# utilidong-lipo-charger-mk-2_1.net
KiCad netlist of a schematic drawn in EAGLE
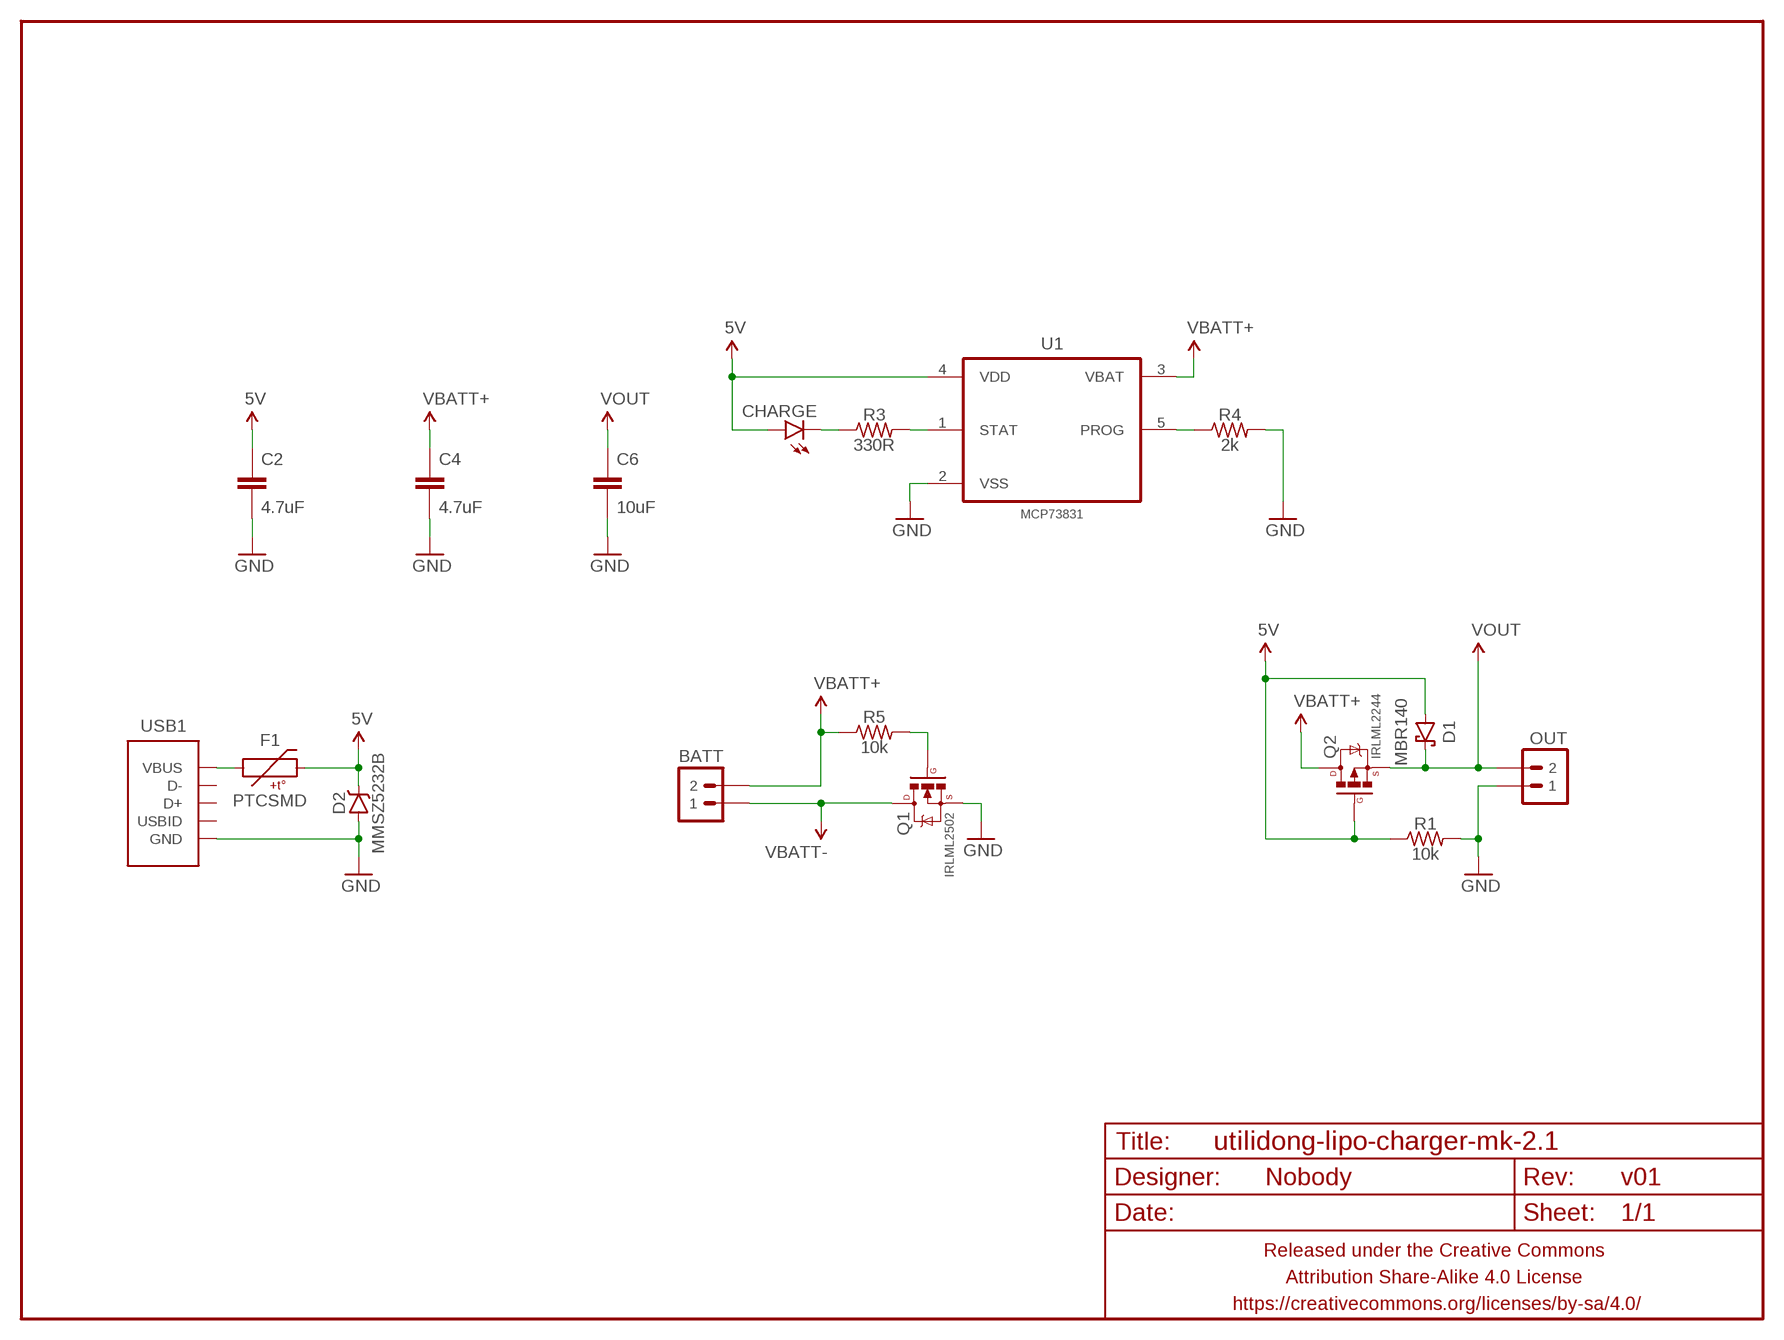
[diagram p0: schematic, sheet 1]

(export (version "E")
  (design (tool "Eeschema 10.0.6"))
  (components
    (comp (ref "BATT")
      (value "M02PTH-CENTERED-R+")
      (footprint "eagle-import:1X02-CENTER-R+")
      (libsource (lib "eagle-import") (part "M02PTH-CENTERED-R+"))
    )
    (comp (ref "C2")
      (value "4.7uF")
      (footprint "eagle-import:C0805")
      (libsource (lib "eagle-import") (part "CAPACITOR-CERAMICC0805"))
    )
    (comp (ref "C4")
      (value "4.7uF")
      (footprint "eagle-import:C0805")
      (libsource (lib "eagle-import") (part "CAPACITOR-CERAMICC0805"))
    )
    (comp (ref "C6")
      (value "10uF")
      (footprint "eagle-import:C0805")
      (libsource (lib "eagle-import") (part "CAPACITOR-CERAMICC0805"))
    )
    (comp (ref "CHARGE")
      (value "LED1206")
      (footprint "eagle-import:LED-1206")
      (libsource (lib "eagle-import") (part "LED1206"))
    )
    (comp (ref "D1")
      (value "MBR140")
      (footprint "eagle-import:SMA-DIODE-SCHOTTKY")
      (libsource (lib "eagle-import") (part "DIODE-SCHOTTKYSMA"))
    )
    (comp (ref "D2")
      (value "MMSZ5232B")
      (footprint "eagle-import:SOD123-ZENER")
      (libsource (lib "eagle-import") (part "DIODE-ZENERSOD123"))
    )
    (comp (ref "F1")
      (value "PTCSMD")
      (footprint "eagle-import:PTC-1206")
      (libsource (lib "eagle-import") (part "PTCSMD"))
    )
    (comp (ref "FRAME1")
      (value "FRAME-LETTERNO_PACKAGE")
      (footprint "eagle-import:DUMMY")
      (fields (field (name "DESIGNER") "Nobody"))
      (libsource (lib "eagle-import") (part "FRAME-LETTERNO_PACKAGE"))
    )
    (comp (ref "OUT")
      (value "M02PTH-CENTERED-R+")
      (footprint "eagle-import:1X02-CENTER-R+")
      (libsource (lib "eagle-import") (part "M02PTH-CENTERED-R+"))
    )
    (comp (ref "Q1")
      (value "IRLML2502")
      (footprint "eagle-import:SOT23")
      (libsource (lib "eagle-import") (part "MOSFET-NCHANNELBSS138"))
    )
    (comp (ref "Q2")
      (value "IRLML2244")
      (footprint "eagle-import:SOT23-3")
      (libsource (lib "eagle-import") (part "MOSFET-PCHANNELIRLML2244"))
    )
    (comp (ref "R1")
      (value "10k")
      (footprint "eagle-import:R0805")
      (libsource (lib "eagle-import") (part "RESISTORR0805"))
    )
    (comp (ref "R3")
      (value "330R")
      (footprint "eagle-import:R0805")
      (libsource (lib "eagle-import") (part "RESISTORR0805"))
    )
    (comp (ref "R4")
      (value "2k")
      (footprint "eagle-import:R0805")
      (libsource (lib "eagle-import") (part "RESISTORR0805"))
    )
    (comp (ref "R5")
      (value "10k")
      (footprint "eagle-import:R0805")
      (libsource (lib "eagle-import") (part "RESISTORR0805"))
    )
    (comp (ref "U1")
      (value "MCP73831")
      (footprint "eagle-import:SOT95P280X145-5N")
      (fields (field (name "MPN") "MCP73831T-2ACI/OT"))
      (libsource (lib "eagle-import") (part "MCP73831T-2ACI/OT"))
    )
    (comp (ref "USB1")
      (value "USB-ABCOMBO")
      (footprint "eagle-import:USB-MICRO-B-FCI-CUTOUT")
      (libsource (lib "eagle-import") (part "USB-ABCOMBO"))
    )
  )
  (nets
    (net (code "1") (name "5V") (class "Default")
      (node (ref "C2") (pin "1") (pinfunction "1_1") (pintype "passive"))
      (node (ref "CHARGE") (pin "A") (pinfunction "A_A") (pintype "passive"))
      (node (ref "D1") (pin "A") (pinfunction "A_A") (pintype "passive"))
      (node (ref "D2") (pin "C") (pinfunction "C_C") (pintype "passive"))
      (node (ref "F1") (pin "2") (pinfunction "2_2") (pintype "passive"))
      (node (ref "Q2") (pin "1") (pinfunction "G_1") (pintype "passive"))
      (node (ref "R1") (pin "1") (pinfunction "1_1") (pintype "passive"))
      (node (ref "U1") (pin "4") (pinfunction "VDD_4") (pintype "power_in"))
    )
    (net (code "2") (name "GND") (class "Default")
      (node (ref "C2") (pin "2") (pinfunction "2_2") (pintype "passive"))
      (node (ref "C4") (pin "2") (pinfunction "2_2") (pintype "passive"))
      (node (ref "C6") (pin "2") (pinfunction "2_2") (pintype "passive"))
      (node (ref "D2") (pin "A") (pinfunction "A_A") (pintype "passive"))
      (node (ref "OUT") (pin "1") (pinfunction "1_1") (pintype "passive"))
      (node (ref "Q1") (pin "2") (pinfunction "S_2") (pintype "passive"))
      (node (ref "R1") (pin "2") (pinfunction "2_2") (pintype "passive"))
      (node (ref "R4") (pin "2") (pinfunction "2_2") (pintype "passive"))
      (node (ref "U1") (pin "2") (pinfunction "VSS_2") (pintype "power_in"))
      (node (ref "USB1") (pin "5") (pinfunction "GND_5") (pintype "bidirectional"))
      (node (ref "USB1") (pin "P$1") (pinfunction "GND_P$1") (pintype "bidirectional"))
      (node (ref "USB1") (pin "P$2") (pinfunction "GND_P$2") (pintype "bidirectional"))
    )
    (net (code "3") (name "Net-(CHARGE-PadC)") (class "Default")
      (node (ref "CHARGE") (pin "C") (pinfunction "C_C") (pintype "passive"))
      (node (ref "R3") (pin "1") (pinfunction "1_1") (pintype "passive"))
    )
    (net (code "4") (name "Net-(Q1-G)") (class "Default")
      (node (ref "Q1") (pin "1") (pinfunction "G_1") (pintype "passive"))
      (node (ref "R5") (pin "2") (pinfunction "2_2") (pintype "passive"))
    )
    (net (code "5") (name "Net-(U1-PROG)") (class "Default")
      (node (ref "R4") (pin "1") (pinfunction "1_1") (pintype "passive"))
      (node (ref "U1") (pin "5") (pinfunction "PROG_5") (pintype "input"))
    )
    (net (code "6") (name "Net-(U1-STAT)") (class "Default")
      (node (ref "R3") (pin "2") (pinfunction "2_2") (pintype "passive"))
      (node (ref "U1") (pin "1") (pinfunction "STAT_1") (pintype "output"))
    )
    (net (code "7") (name "Net-(USB1-VBUS)") (class "Default")
      (node (ref "F1") (pin "1") (pinfunction "1_1") (pintype "passive"))
      (node (ref "USB1") (pin "1") (pinfunction "VBUS_1") (pintype "bidirectional"))
    )
    (net (code "8") (name "VBATT+") (class "Default")
      (node (ref "BATT") (pin "2") (pinfunction "2_2") (pintype "passive"))
      (node (ref "C4") (pin "1") (pinfunction "1_1") (pintype "passive"))
      (node (ref "Q2") (pin "3") (pinfunction "D_3") (pintype "passive"))
      (node (ref "R5") (pin "1") (pinfunction "1_1") (pintype "passive"))
      (node (ref "U1") (pin "3") (pinfunction "VBAT_3") (pintype "output"))
    )
    (net (code "9") (name "VBATT-") (class "Default")
      (node (ref "BATT") (pin "1") (pinfunction "1_1") (pintype "passive"))
      (node (ref "Q1") (pin "3") (pinfunction "D_3") (pintype "passive"))
    )
    (net (code "10") (name "VOUT") (class "Default")
      (node (ref "C6") (pin "1") (pinfunction "1_1") (pintype "passive"))
      (node (ref "D1") (pin "C") (pinfunction "C_C") (pintype "passive"))
      (node (ref "OUT") (pin "2") (pinfunction "2_2") (pintype "passive"))
      (node (ref "Q2") (pin "2") (pinfunction "S_2") (pintype "passive"))
    )
    (net (code "11") (name "unconnected-(USB1-D+-Pad3)") (class "Default")
      (node (ref "USB1") (pin "3") (pinfunction "D+_3") (pintype "bidirectional"))
    )
    (net (code "12") (name "unconnected-(USB1-D--Pad2)") (class "Default")
      (node (ref "USB1") (pin "2") (pinfunction "D-_2") (pintype "bidirectional"))
    )
    (net (code "13") (name "unconnected-(USB1-USBID-Pad4)") (class "Default")
      (node (ref "USB1") (pin "4") (pinfunction "USBID_4") (pintype "bidirectional"))
    )
  )
)
